# attiny_bootloader.net
KiCad netlist of a schematic drawn in EAGLE
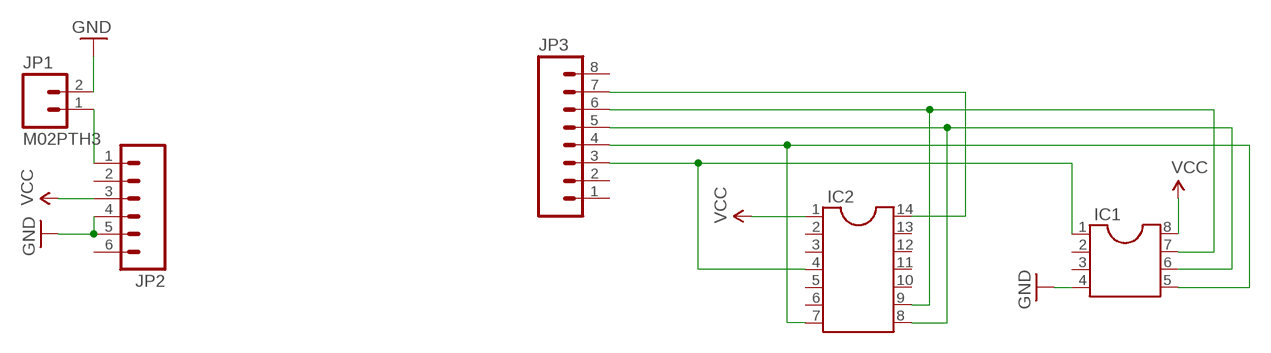
[diagram p0: schematic, sheet 1]

(export (version "E")
  (design (tool "Eeschema 10.0.6"))
  (components
    (comp (ref "IC1")
      (value "DIL8S")
      (footprint "eagle-import:SOCKET-08")
      (libsource (lib "eagle-import") (part "DIL8S"))
    )
    (comp (ref "IC2")
      (value "DIL14S")
      (footprint "eagle-import:SOCKET-14")
      (libsource (lib "eagle-import") (part "DIL14S"))
    )
    (comp (ref "JP1")
      (value "M02PTH3")
      (footprint "eagle-import:1X02_LONGPADS")
      (libsource (lib "eagle-import") (part "M02PTH3"))
    )
    (comp (ref "JP2")
      (value "M06LONGPADS")
      (footprint "eagle-import:1X06_LONGPADS")
      (libsource (lib "eagle-import") (part "M06LONGPADS"))
    )
    (comp (ref "JP3")
      (value "M08LONGPADS")
      (footprint "eagle-import:1X08_LONGPADS")
      (libsource (lib "eagle-import") (part "M08LONGPADS"))
    )
  )
  (nets
    (net (code "1") (name "GND") (class "Default")
      (node (ref "IC1") (pin "4") (pinfunction "4_4") (pintype "passive"))
      (node (ref "JP1") (pin "2") (pinfunction "2_2") (pintype "passive"))
      (node (ref "JP2") (pin "4") (pinfunction "4_4") (pintype "passive"))
      (node (ref "JP2") (pin "5") (pinfunction "5_5") (pintype "passive"))
    )
    (net (code "2") (name "Net-(IC1-Pad1)") (class "Default")
      (node (ref "IC1") (pin "1") (pinfunction "1_1") (pintype "passive"))
      (node (ref "IC2") (pin "4") (pinfunction "4_4") (pintype "passive"))
      (node (ref "JP3") (pin "3") (pinfunction "3_3") (pintype "passive"))
    )
    (net (code "3") (name "Net-(IC1-Pad5)") (class "Default")
      (node (ref "IC1") (pin "5") (pinfunction "5_5") (pintype "passive"))
      (node (ref "IC2") (pin "7") (pinfunction "7_7") (pintype "passive"))
      (node (ref "JP3") (pin "4") (pinfunction "4_4") (pintype "passive"))
    )
    (net (code "4") (name "Net-(IC1-Pad6)") (class "Default")
      (node (ref "IC1") (pin "6") (pinfunction "6_6") (pintype "passive"))
      (node (ref "IC2") (pin "8") (pinfunction "8_8") (pintype "passive"))
      (node (ref "JP3") (pin "5") (pinfunction "5_5") (pintype "passive"))
    )
    (net (code "5") (name "Net-(IC1-Pad7)") (class "Default")
      (node (ref "IC1") (pin "7") (pinfunction "7_7") (pintype "passive"))
      (node (ref "IC2") (pin "9") (pinfunction "9_9") (pintype "passive"))
      (node (ref "JP3") (pin "6") (pinfunction "6_6") (pintype "passive"))
    )
    (net (code "6") (name "Net-(IC2-Pad14)") (class "Default")
      (node (ref "IC2") (pin "14") (pinfunction "14_14") (pintype "passive"))
      (node (ref "JP3") (pin "7") (pinfunction "7_7") (pintype "passive"))
    )
    (net (code "7") (name "Net-(JP1-Pad1)") (class "Default")
      (node (ref "JP1") (pin "1") (pinfunction "1_1") (pintype "passive"))
      (node (ref "JP2") (pin "1") (pinfunction "1_1") (pintype "passive"))
    )
    (net (code "8") (name "VCC") (class "Default")
      (node (ref "IC1") (pin "8") (pinfunction "8_8") (pintype "passive"))
      (node (ref "IC2") (pin "1") (pinfunction "1_1") (pintype "passive"))
      (node (ref "JP2") (pin "3") (pinfunction "3_3") (pintype "passive"))
    )
    (net (code "9") (name "unconnected-(IC1-Pad2)") (class "Default")
      (node (ref "IC1") (pin "2") (pinfunction "2_2") (pintype "passive"))
    )
    (net (code "10") (name "unconnected-(IC1-Pad3)") (class "Default")
      (node (ref "IC1") (pin "3") (pinfunction "3_3") (pintype "passive"))
    )
    (net (code "11") (name "unconnected-(IC2-Pad2)") (class "Default")
      (node (ref "IC2") (pin "2") (pinfunction "2_2") (pintype "passive"))
    )
    (net (code "12") (name "unconnected-(IC2-Pad3)") (class "Default")
      (node (ref "IC2") (pin "3") (pinfunction "3_3") (pintype "passive"))
    )
    (net (code "13") (name "unconnected-(IC2-Pad5)") (class "Default")
      (node (ref "IC2") (pin "5") (pinfunction "5_5") (pintype "passive"))
    )
    (net (code "14") (name "unconnected-(IC2-Pad6)") (class "Default")
      (node (ref "IC2") (pin "6") (pinfunction "6_6") (pintype "passive"))
    )
    (net (code "15") (name "unconnected-(IC2-Pad10)") (class "Default")
      (node (ref "IC2") (pin "10") (pinfunction "10_10") (pintype "passive"))
    )
    (net (code "16") (name "unconnected-(IC2-Pad11)") (class "Default")
      (node (ref "IC2") (pin "11") (pinfunction "11_11") (pintype "passive"))
    )
    (net (code "17") (name "unconnected-(IC2-Pad12)") (class "Default")
      (node (ref "IC2") (pin "12") (pinfunction "12_12") (pintype "passive"))
    )
    (net (code "18") (name "unconnected-(IC2-Pad13)") (class "Default")
      (node (ref "IC2") (pin "13") (pinfunction "13_13") (pintype "passive"))
    )
    (net (code "19") (name "unconnected-(JP2-Pad2)") (class "Default")
      (node (ref "JP2") (pin "2") (pinfunction "2_2") (pintype "passive"))
    )
    (net (code "20") (name "unconnected-(JP2-Pad6)") (class "Default")
      (node (ref "JP2") (pin "6") (pinfunction "6_6") (pintype "passive"))
    )
    (net (code "21") (name "unconnected-(JP3-Pad1)") (class "Default")
      (node (ref "JP3") (pin "1") (pinfunction "1_1") (pintype "passive"))
    )
    (net (code "22") (name "unconnected-(JP3-Pad2)") (class "Default")
      (node (ref "JP3") (pin "2") (pinfunction "2_2") (pintype "passive"))
    )
    (net (code "23") (name "unconnected-(JP3-Pad8)") (class "Default")
      (node (ref "JP3") (pin "8") (pinfunction "8_8") (pintype "passive"))
    )
  )
)
